# soldering_station.net
KiCad netlist of a schematic drawn in Altium Designer
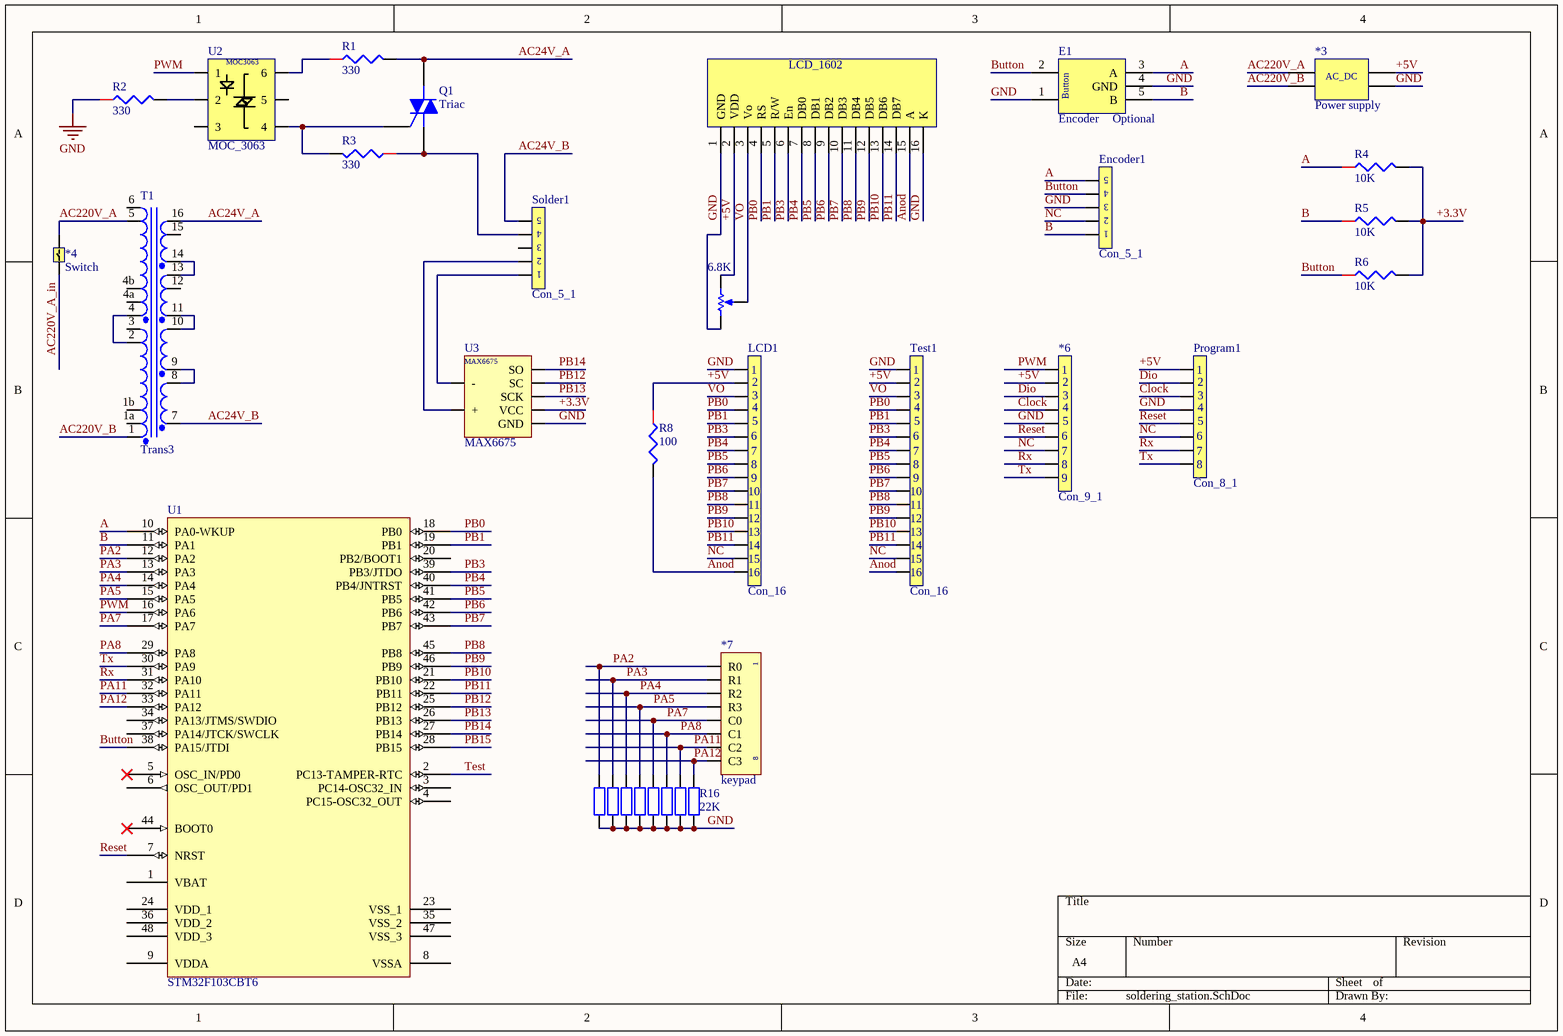
[diagram p0: soldering_station.SchDoc]

(export (version "E")
  (design (tool "Eeschema 10.0.6"))
  (components
    (comp (ref "*2") (value "LCD_1602") (libsource (lib "Armen_1") (part "LCD_1602")))
    (comp (ref "*3") (value "Power supply") (libsource (lib "Armen_1") (part "Power supply")))
    (comp (ref "*4") (value "Switch") (libsource (lib "Armen_1") (part "Switch_3_small")))
    (comp (ref "*6") (value "Con_9_1") (libsource (lib "Armen_1") (part "Con_9_1")))
    (comp (ref "*7") (value "keypad") (libsource (lib "Armen_1") (part "keypad")))
    (comp (ref "E1") (value "Encoder") (libsource (lib "Armen_1") (part "Encoder")))
    (comp (ref "Encoder1") (value "Con_5_1") (libsource (lib "Armen_1") (part "Con_5_1")))
    (comp (ref "LCD1") (value "Con_16") (libsource (lib "Armen_1") (part "Con_16")))
    (comp (ref "Program1") (value "Con_8_1") (libsource (lib "Armen_1") (part "Con_8_1")))
    (comp (ref "Q1")
      (value "Triac")
      (footprint "369-03")
      (description "Silicon Bidirectional Triode Thyristor")
      (fields (field (name "PUBLISHER") "Altium Limited"))
      (libsource (lib "Miscellaneous Devices") (part "Triac"))
    )
    (comp (ref "R1")
      (value "330")
      (footprint "Chip2PinSM127P600-8N")
      (description "RES SMD 1K OHM 0.1% 1/10W 0603")
      (fields
        (field (name "DIGI-KEY PART NUMBER") "P1.0KDBCT-ND")
        (field (name "MANUFACTURER PART NUMBER") "ERA-3AEB102V")
      )
      (libsource (lib "Wash_Control") (part "Resistor_1K"))
    )
    (comp (ref "R2")
      (value "330")
      (footprint "Chip2PinSM127P600-8N")
      (description "RES SMD 1K OHM 0.1% 1/10W 0603")
      (fields
        (field (name "DIGI-KEY PART NUMBER") "P1.0KDBCT-ND")
        (field (name "MANUFACTURER PART NUMBER") "ERA-3AEB102V")
      )
      (libsource (lib "Wash_Control") (part "Resistor_1K"))
    )
    (comp (ref "R3")
      (value "330")
      (footprint "Chip2PinSM127P600-8N")
      (description "RES SMD 1K OHM 0.1% 1/10W 0603")
      (fields
        (field (name "DIGI-KEY PART NUMBER") "P1.0KDBCT-ND")
        (field (name "MANUFACTURER PART NUMBER") "ERA-3AEB102V")
      )
      (libsource (lib "Wash_Control") (part "Resistor_1K"))
    )
    (comp (ref "R4")
      (value "10K")
      (footprint "Chip2PinSM127P600-8N")
      (description "RES SMD 10K OHM 0.5% 1/16W 0603")
      (fields
        (field (name "DIGI-KEY PART NUMBER") "RR08P10.0KDTR-ND")
        (field (name "MANUFACTURER PART NUMBER") "RR0816P-103-D")
      )
      (libsource (lib "Wash_Control") (part "Resistor_10k Ohm"))
    )
    (comp (ref "R5")
      (value "10K")
      (footprint "Chip2PinSM127P600-8N")
      (description "RES SMD 10K OHM 0.5% 1/16W 0603")
      (fields
        (field (name "DIGI-KEY PART NUMBER") "RR08P10.0KDTR-ND")
        (field (name "MANUFACTURER PART NUMBER") "RR0816P-103-D")
      )
      (libsource (lib "Wash_Control") (part "Resistor_10k Ohm"))
    )
    (comp (ref "R6")
      (value "10K")
      (footprint "Chip2PinSM127P600-8N")
      (description "RES SMD 10K OHM 0.5% 1/16W 0603")
      (fields
        (field (name "DIGI-KEY PART NUMBER") "RR08P10.0KDTR-ND")
        (field (name "MANUFACTURER PART NUMBER") "RR0816P-103-D")
      )
      (libsource (lib "Wash_Control") (part "Resistor_10k Ohm"))
    )
    (comp (ref "R7")
      (value "6.8K")
      (footprint "VR5")
      (description "Potentiometer")
      (fields (field (name "Comment") "RPot") (field (name "PUBLISHER") "Altium Limited"))
      (libsource (lib "Miscellaneous Devices") (part "RPot"))
    )
    (comp (ref "R8")
      (value "100")
      (footprint "Chip2PinSM127P600-8N")
      (description "RES SMD 1K OHM 0.1% 1/10W 0603")
      (fields
        (field (name "DIGI-KEY PART NUMBER") "P1.0KDBCT-ND")
        (field (name "MANUFACTURER PART NUMBER") "ERA-3AEB102V")
      )
      (libsource (lib "Wash_Control") (part "Resistor_1K"))
    )
    (comp (ref "R9")
      (value "20K")
      (footprint "AXIAL-0.4")
      (description "Resistor")
      (libsource (lib "Ar_MainBoard_RPD_") (part "Res2"))
    )
    (comp (ref "R10")
      (value "20K")
      (footprint "AXIAL-0.4")
      (description "Resistor")
      (libsource (lib "Ar_MainBoard_RPD_") (part "Res2"))
    )
    (comp (ref "R11")
      (value "20K")
      (footprint "AXIAL-0.4")
      (description "Resistor")
      (libsource (lib "Ar_MainBoard_RPD_") (part "Res2"))
    )
    (comp (ref "R12")
      (value "20K")
      (footprint "AXIAL-0.4")
      (description "Resistor")
      (libsource (lib "Ar_MainBoard_RPD_") (part "Res2"))
    )
    (comp (ref "R13")
      (value "20K")
      (footprint "AXIAL-0.4")
      (description "Resistor")
      (libsource (lib "Ar_MainBoard_RPD_") (part "Res2"))
    )
    (comp (ref "R14")
      (value "20K")
      (footprint "AXIAL-0.4")
      (description "Resistor")
      (libsource (lib "Ar_MainBoard_RPD_") (part "Res2"))
    )
    (comp (ref "R15")
      (value "20K")
      (footprint "AXIAL-0.4")
      (description "Resistor")
      (libsource (lib "Ar_MainBoard_RPD_") (part "Res2"))
    )
    (comp (ref "R16")
      (value "22K")
      (footprint "AXIAL-0.4")
      (description "Resistor")
      (libsource (lib "Ar_MainBoard_RPD_") (part "Res2"))
    )
    (comp (ref "Solder1") (value "Con_5_1") (libsource (lib "Armen_1") (part "Con_5_1")))
    (comp (ref "T1")
      (value "Trans3")
      (footprint "TRF_6")
      (description "Three-winding Transformer (Non-Ideal)")
      (fields (field (name "PUBLISHER") "Altium Limited"))
      (libsource (lib "Soldering_station") (part "Trans3_1"))
    )
    (comp (ref "Test1") (value "Con_16") (libsource (lib "Armen_1") (part "Con_16")))
    (comp (ref "U1")
      (value "STM32F103CBT6")
      (footprint "LQFP48_N")
      (description "STM32 ARM-based 32-bit MCU with 128 Kbytes Flash, 48-pin LQFP, Industrial Temperature")
      (fields (field (name "PUBLISHER") "Altium Limited"))
      (libsource (lib "ST Microcontroller 32-Bit STM32") (part "STM32F103CBT6"))
    )
    (comp (ref "U2") (value "MOC_3063") (libsource (lib "Soldering_station") (part "MOC_3065")))
    (comp (ref "U3") (value "MAX6675") (libsource (lib "Armen_1") (part "MAX6675")))
  )
  (nets
    (net (code "1") (name "/+3.3V") (class "Default")
      (node (ref "R4") (pin "2") (pinfunction "2_2") (pintype "passive"))
      (node (ref "R5") (pin "2") (pinfunction "2_2") (pintype "passive"))
      (node (ref "R6") (pin "2") (pinfunction "2_2") (pintype "passive"))
      (node (ref "U3") (pin "6") (pinfunction "VCC_6") (pintype "passive"))
    )
    (net (code "2") (name "/+5V") (class "Default")
      (node (ref "*2") (pin "2") (pinfunction "VDD_2") (pintype "passive"))
      (node (ref "*3") (pin "30") (pinfunction "30_30") (pintype "passive"))
      (node (ref "*6") (pin "2") (pinfunction "2_2") (pintype "passive"))
      (node (ref "LCD1") (pin "2") (pinfunction "2_2") (pintype "passive"))
      (node (ref "Program1") (pin "1") (pinfunction "1_1") (pintype "passive"))
      (node (ref "R7") (pin "2") (pinfunction "BOT_2") (pintype "passive"))
      (node (ref "R8") (pin "1") (pinfunction "1_1") (pintype "passive"))
      (node (ref "Test1") (pin "2") (pinfunction "2_2") (pintype "passive"))
    )
    (net (code "3") (name "/A") (class "Default")
      (node (ref "E1") (pin "3") (pinfunction "A_3") (pintype "passive"))
      (node (ref "Encoder1") (pin "4") (pinfunction "4_4") (pintype "passive"))
      (node (ref "R4") (pin "1") (pinfunction "1_1") (pintype "passive"))
      (node (ref "U1") (pin "10") (pinfunction "PA0-WKUP_10") (pintype "bidirectional"))
    )
    (net (code "4") (name "/AC24V_A") (class "Default")
      (node (ref "Q1") (pin "2") (pinfunction "M2_2") (pintype "passive"))
      (node (ref "R1") (pin "2") (pinfunction "2_2") (pintype "passive"))
      (node (ref "T1") (pin "16") (pinfunction "16_16") (pintype "passive"))
    )
    (net (code "5") (name "/AC24V_B") (class "Default")
      (node (ref "Solder1") (pin "4") (pinfunction "4_4") (pintype "passive"))
      (node (ref "T1") (pin "7") (pinfunction "7_7") (pintype "passive"))
    )
    (net (code "6") (name "/AC220V_A") (class "Default")
      (node (ref "*3") (pin "32") (pinfunction "32_32") (pintype "passive"))
      (node (ref "*4") (pin "35") (pinfunction "35_35") (pintype "passive"))
      (node (ref "T1") (pin "5") (pinfunction "5_5") (pintype "passive"))
    )
    (net (code "7") (name "/AC220V_A_in") (class "Default")
      (node (ref "*4") (pin "34") (pinfunction "34_34") (pintype "passive"))
    )
    (net (code "8") (name "/AC220V_B") (class "Default")
      (node (ref "*3") (pin "33") (pinfunction "33_33") (pintype "passive"))
      (node (ref "T1") (pin "1") (pinfunction "1_1") (pintype "passive"))
    )
    (net (code "9") (name "/Anod") (class "Default")
      (node (ref "*2") (pin "15") (pinfunction "A_15") (pintype "passive"))
      (node (ref "LCD1") (pin "16") (pinfunction "16_16") (pintype "passive"))
      (node (ref "R8") (pin "2") (pinfunction "2_2") (pintype "passive"))
      (node (ref "Test1") (pin "16") (pinfunction "16_16") (pintype "passive"))
    )
    (net (code "10") (name "/B") (class "Default")
      (node (ref "E1") (pin "5") (pinfunction "B_5") (pintype "passive"))
      (node (ref "Encoder1") (pin "0") (pinfunction "0_0") (pintype "passive"))
      (node (ref "R5") (pin "1") (pinfunction "1_1") (pintype "passive"))
      (node (ref "U1") (pin "11") (pinfunction "PA1_11") (pintype "bidirectional"))
    )
    (net (code "11") (name "/Button") (class "Default")
      (node (ref "E1") (pin "2") (pintype "passive"))
      (node (ref "Encoder1") (pin "3") (pinfunction "3_3") (pintype "passive"))
      (node (ref "R6") (pin "1") (pinfunction "1_1") (pintype "passive"))
      (node (ref "U1") (pin "38") (pinfunction "PA15/JTDI_38") (pintype "bidirectional"))
    )
    (net (code "12") (name "/Clock") (class "Default")
      (node (ref "*6") (pin "4") (pinfunction "4_4") (pintype "passive"))
      (node (ref "Program1") (pin "3") (pinfunction "3_3") (pintype "passive"))
    )
    (net (code "13") (name "/Dio") (class "Default")
      (node (ref "*6") (pin "3") (pinfunction "3_3") (pintype "passive"))
      (node (ref "Program1") (pin "2") (pinfunction "2_2") (pintype "passive"))
    )
    (net (code "14") (name "/NC") (class "Default")
      (node (ref "*6") (pin "7") (pinfunction "7_7") (pintype "passive"))
      (node (ref "Encoder1") (pin "1") (pinfunction "1_1") (pintype "passive"))
      (node (ref "LCD1") (pin "15") (pinfunction "15_15") (pintype "passive"))
      (node (ref "Program1") (pin "6") (pinfunction "6_6") (pintype "passive"))
      (node (ref "Test1") (pin "15") (pinfunction "15_15") (pintype "passive"))
    )
    (net (code "15") (name "/PA2") (class "Default")
      (node (ref "*7") (pin "1") (pinfunction "R0_1") (pintype "passive"))
      (node (ref "R9") (pin "2") (pinfunction "2_2") (pintype "passive"))
      (node (ref "U1") (pin "12") (pinfunction "PA2_12") (pintype "bidirectional"))
    )
    (net (code "16") (name "/PA3") (class "Default")
      (node (ref "*7") (pin "2") (pinfunction "R1_2") (pintype "passive"))
      (node (ref "R10") (pin "2") (pinfunction "2_2") (pintype "passive"))
      (node (ref "U1") (pin "13") (pinfunction "PA3_13") (pintype "bidirectional"))
    )
    (net (code "17") (name "/PA4") (class "Default")
      (node (ref "*7") (pin "3") (pinfunction "R2_3") (pintype "passive"))
      (node (ref "R11") (pin "2") (pinfunction "2_2") (pintype "passive"))
      (node (ref "U1") (pin "14") (pinfunction "PA4_14") (pintype "bidirectional"))
    )
    (net (code "18") (name "/PA5") (class "Default")
      (node (ref "*7") (pin "4") (pinfunction "R3_4") (pintype "passive"))
      (node (ref "R12") (pin "2") (pinfunction "2_2") (pintype "passive"))
      (node (ref "U1") (pin "15") (pinfunction "PA5_15") (pintype "bidirectional"))
    )
    (net (code "19") (name "/PA7") (class "Default")
      (node (ref "*7") (pin "5") (pinfunction "C0_5") (pintype "passive"))
      (node (ref "R13") (pin "2") (pinfunction "2_2") (pintype "passive"))
      (node (ref "U1") (pin "17") (pinfunction "PA7_17") (pintype "bidirectional"))
    )
    (net (code "20") (name "/PA8") (class "Default")
      (node (ref "*7") (pin "6") (pinfunction "C1_6") (pintype "passive"))
      (node (ref "R14") (pin "2") (pinfunction "2_2") (pintype "passive"))
      (node (ref "U1") (pin "29") (pinfunction "PA8_29") (pintype "bidirectional"))
    )
    (net (code "21") (name "/PA11") (class "Default")
      (node (ref "*7") (pin "7") (pinfunction "C2_7") (pintype "passive"))
      (node (ref "R15") (pin "2") (pinfunction "2_2") (pintype "passive"))
      (node (ref "U1") (pin "32") (pinfunction "PA11_32") (pintype "bidirectional"))
    )
    (net (code "22") (name "/PA12") (class "Default")
      (node (ref "*7") (pin "8") (pinfunction "C3_8") (pintype "passive"))
      (node (ref "R16") (pin "2") (pinfunction "2_2") (pintype "passive"))
      (node (ref "U1") (pin "33") (pinfunction "PA12_33") (pintype "bidirectional"))
    )
    (net (code "23") (name "/PB0") (class "Default")
      (node (ref "*2") (pin "4") (pinfunction "RS_4") (pintype "passive"))
      (node (ref "LCD1") (pin "4") (pinfunction "4_4") (pintype "passive"))
      (node (ref "Test1") (pin "4") (pinfunction "4_4") (pintype "passive"))
      (node (ref "U1") (pin "18") (pinfunction "PB0_18") (pintype "bidirectional"))
    )
    (net (code "24") (name "/PB1") (class "Default")
      (node (ref "*2") (pin "5") (pinfunction "R/W_5") (pintype "passive"))
      (node (ref "LCD1") (pin "5") (pinfunction "5_5") (pintype "passive"))
      (node (ref "Test1") (pin "5") (pinfunction "5_5") (pintype "passive"))
      (node (ref "U1") (pin "19") (pinfunction "PB1_19") (pintype "bidirectional"))
    )
    (net (code "25") (name "/PB3") (class "Default")
      (node (ref "*2") (pin "6") (pinfunction "En_6") (pintype "passive"))
      (node (ref "LCD1") (pin "6") (pinfunction "6_6") (pintype "passive"))
      (node (ref "Test1") (pin "6") (pinfunction "6_6") (pintype "passive"))
      (node (ref "U1") (pin "39") (pinfunction "PB3/JTDO_39") (pintype "bidirectional"))
    )
    (net (code "26") (name "/PB4") (class "Default")
      (node (ref "*2") (pin "7") (pinfunction "DB0_7") (pintype "passive"))
      (node (ref "LCD1") (pin "7") (pinfunction "7_7") (pintype "passive"))
      (node (ref "Test1") (pin "7") (pinfunction "7_7") (pintype "passive"))
      (node (ref "U1") (pin "40") (pinfunction "PB4/JNTRST_40") (pintype "bidirectional"))
    )
    (net (code "27") (name "/PB5") (class "Default")
      (node (ref "*2") (pin "8") (pinfunction "DB1_8") (pintype "passive"))
      (node (ref "LCD1") (pin "8") (pinfunction "8_8") (pintype "passive"))
      (node (ref "Test1") (pin "8") (pinfunction "8_8") (pintype "passive"))
      (node (ref "U1") (pin "41") (pinfunction "PB5_41") (pintype "bidirectional"))
    )
    (net (code "28") (name "/PB6") (class "Default")
      (node (ref "*2") (pin "9") (pinfunction "DB2_9") (pintype "passive"))
      (node (ref "LCD1") (pin "9") (pinfunction "9_9") (pintype "passive"))
      (node (ref "Test1") (pin "9") (pinfunction "9_9") (pintype "passive"))
      (node (ref "U1") (pin "42") (pinfunction "PB6_42") (pintype "bidirectional"))
    )
    (net (code "29") (name "/PB7") (class "Default")
      (node (ref "*2") (pin "10") (pinfunction "DB3_10") (pintype "passive"))
      (node (ref "LCD1") (pin "10") (pinfunction "10_10") (pintype "passive"))
      (node (ref "Test1") (pin "10") (pinfunction "10_10") (pintype "passive"))
      (node (ref "U1") (pin "43") (pinfunction "PB7_43") (pintype "bidirectional"))
    )
    (net (code "30") (name "/PB8") (class "Default")
      (node (ref "*2") (pin "11") (pinfunction "DB4_11") (pintype "passive"))
      (node (ref "LCD1") (pin "11") (pinfunction "11_11") (pintype "passive"))
      (node (ref "Test1") (pin "11") (pinfunction "11_11") (pintype "passive"))
      (node (ref "U1") (pin "45") (pinfunction "PB8_45") (pintype "bidirectional"))
    )
    (net (code "31") (name "/PB9") (class "Default")
      (node (ref "*2") (pin "12") (pinfunction "DB5_12") (pintype "passive"))
      (node (ref "LCD1") (pin "12") (pinfunction "12_12") (pintype "passive"))
      (node (ref "Test1") (pin "12") (pinfunction "12_12") (pintype "passive"))
      (node (ref "U1") (pin "46") (pinfunction "PB9_46") (pintype "bidirectional"))
    )
    (net (code "32") (name "/PB10") (class "Default")
      (node (ref "*2") (pin "13") (pinfunction "DB6_13") (pintype "passive"))
      (node (ref "LCD1") (pin "13") (pinfunction "13_13") (pintype "passive"))
      (node (ref "Test1") (pin "13") (pinfunction "13_13") (pintype "passive"))
      (node (ref "U1") (pin "21") (pinfunction "PB10_21") (pintype "bidirectional"))
    )
    (net (code "33") (name "/PB11") (class "Default")
      (node (ref "*2") (pin "14") (pinfunction "DB7_14") (pintype "passive"))
      (node (ref "LCD1") (pin "14") (pinfunction "14_14") (pintype "passive"))
      (node (ref "Test1") (pin "14") (pinfunction "14_14") (pintype "passive"))
      (node (ref "U1") (pin "22") (pinfunction "PB11_22") (pintype "bidirectional"))
    )
    (net (code "34") (name "/PB12") (class "Default")
      (node (ref "U1") (pin "25") (pinfunction "PB12_25") (pintype "bidirectional"))
      (node (ref "U3") (pin "4") (pinfunction "SC_4") (pintype "passive"))
    )
    (net (code "35") (name "/PB13") (class "Default")
      (node (ref "U1") (pin "26") (pinfunction "PB13_26") (pintype "bidirectional"))
      (node (ref "U3") (pin "5") (pinfunction "SCK_5") (pintype "passive"))
    )
    (net (code "36") (name "/PB14") (class "Default")
      (node (ref "U1") (pin "27") (pinfunction "PB14_27") (pintype "bidirectional"))
      (node (ref "U3") (pin "3") (pinfunction "SO_3") (pintype "passive"))
    )
    (net (code "37") (name "/PB15") (class "Default")
      (node (ref "U1") (pin "28") (pinfunction "PB15_28") (pintype "bidirectional"))
    )
    (net (code "38") (name "/PWM") (class "Default")
      (node (ref "*6") (pin "1") (pinfunction "1_1") (pintype "passive"))
      (node (ref "U1") (pin "16") (pinfunction "PA6_16") (pintype "bidirectional"))
      (node (ref "U2") (pin "1") (pinfunction "1_1") (pintype "passive"))
    )
    (net (code "39") (name "/Reset") (class "Default")
      (node (ref "*6") (pin "6") (pinfunction "6_6") (pintype "passive"))
      (node (ref "Program1") (pin "5") (pinfunction "5_5") (pintype "passive"))
      (node (ref "U1") (pin "7") (pinfunction "NRST_7") (pintype "bidirectional"))
    )
    (net (code "40") (name "/Rx") (class "Default")
      (node (ref "*6") (pin "8") (pinfunction "8_8") (pintype "passive"))
      (node (ref "Program1") (pin "7") (pinfunction "7_7") (pintype "passive"))
      (node (ref "U1") (pin "31") (pinfunction "PA10_31") (pintype "bidirectional"))
    )
    (net (code "41") (name "/Test") (class "Default")
      (node (ref "U1") (pin "2") (pinfunction "PC13-TAMPER-RTC_2") (pintype "bidirectional"))
    )
    (net (code "42") (name "/Tx") (class "Default")
      (node (ref "*6") (pin "9") (pinfunction "9_9") (pintype "passive"))
      (node (ref "Program1") (pin "8") (pinfunction "8_8") (pintype "passive"))
      (node (ref "U1") (pin "30") (pinfunction "PA9_30") (pintype "bidirectional"))
    )
    (net (code "43") (name "/VO") (class "Default")
      (node (ref "*2") (pin "3") (pinfunction "Vo_3") (pintype "passive"))
      (node (ref "LCD1") (pin "3") (pinfunction "3_3") (pintype "passive"))
      (node (ref "R7") (pin "3") (pinfunction "TAP_3") (pintype "passive"))
      (node (ref "Test1") (pin "3") (pinfunction "3_3") (pintype "passive"))
    )
    (net (code "44") (name "GND") (class "Default")
      (node (ref "*2") (pin "1") (pinfunction "GND_1") (pintype "passive"))
      (node (ref "*2") (pin "16") (pinfunction "K_16") (pintype "passive"))
      (node (ref "*3") (pin "31") (pinfunction "31_31") (pintype "passive"))
      (node (ref "*6") (pin "5") (pinfunction "5_5") (pintype "passive"))
      (node (ref "E1") (pin "1") (pintype "passive"))
      (node (ref "E1") (pin "4") (pinfunction "GND_4") (pintype "passive"))
      (node (ref "Encoder1") (pin "2") (pinfunction "2_2") (pintype "passive"))
      (node (ref "LCD1") (pin "1") (pinfunction "1_1") (pintype "passive"))
      (node (ref "Program1") (pin "4") (pinfunction "4_4") (pintype "passive"))
      (node (ref "R10") (pin "1") (pinfunction "1_1") (pintype "passive"))
      (node (ref "R11") (pin "1") (pinfunction "1_1") (pintype "passive"))
      (node (ref "R12") (pin "1") (pinfunction "1_1") (pintype "passive"))
      (node (ref "R13") (pin "1") (pinfunction "1_1") (pintype "passive"))
      (node (ref "R14") (pin "1") (pinfunction "1_1") (pintype "passive"))
      (node (ref "R15") (pin "1") (pinfunction "1_1") (pintype "passive"))
      (node (ref "R16") (pin "1") (pinfunction "1_1") (pintype "passive"))
      (node (ref "R2") (pin "1") (pinfunction "1_1") (pintype "passive"))
      (node (ref "R7") (pin "1") (pinfunction "TOP_1") (pintype "passive"))
      (node (ref "R9") (pin "1") (pinfunction "1_1") (pintype "passive"))
      (node (ref "Test1") (pin "1") (pinfunction "1_1") (pintype "passive"))
      (node (ref "U3") (pin "7") (pinfunction "GND_7") (pintype "passive"))
    )
    (net (code "45") (name "Net-(Q1-G)") (class "Default")
      (node (ref "Q1") (pin "3") (pinfunction "G_3") (pintype "passive"))
      (node (ref "R3") (pin "2") (pinfunction "2_2") (pintype "passive"))
      (node (ref "U2") (pin "4") (pinfunction "4_4") (pintype "passive"))
    )
    (net (code "46") (name "Net-(Q1-M1)") (class "Default")
      (node (ref "Q1") (pin "1") (pinfunction "M1_1") (pintype "passive"))
      (node (ref "R3") (pin "1") (pinfunction "1_1") (pintype "passive"))
      (node (ref "Solder1") (pin "3") (pinfunction "3_3") (pintype "passive"))
    )
    (net (code "47") (name "Net-(R1-Pad1)") (class "Default")
      (node (ref "R1") (pin "1") (pinfunction "1_1") (pintype "passive"))
      (node (ref "U2") (pin "6") (pinfunction "6_6") (pintype "passive"))
    )
    (net (code "48") (name "Net-(R2-Pad2)") (class "Default")
      (node (ref "R2") (pin "2") (pinfunction "2_2") (pintype "passive"))
      (node (ref "U2") (pin "2") (pinfunction "2_2") (pintype "passive"))
    )
    (net (code "49") (name "Net-(T1-Pad2)") (class "Default")
      (node (ref "T1") (pin "2") (pinfunction "2_2") (pintype "passive"))
      (node (ref "T1") (pin "4") (pinfunction "4_4") (pintype "passive"))
    )
    (net (code "50") (name "Net-(T1-Pad8)") (class "Default")
      (node (ref "T1") (pin "8") (pinfunction "8_8") (pintype "passive"))
      (node (ref "T1") (pin "9") (pinfunction "9_9") (pintype "passive"))
    )
    (net (code "51") (name "Net-(T1-Pad10)") (class "Default")
      (node (ref "T1") (pin "10") (pinfunction "10_10") (pintype "passive"))
      (node (ref "T1") (pin "11") (pinfunction "11_11") (pintype "passive"))
    )
    (net (code "52") (name "Net-(T1-Pad13)") (class "Default")
      (node (ref "T1") (pin "13") (pinfunction "13_13") (pintype "passive"))
      (node (ref "T1") (pin "14") (pinfunction "14_14") (pintype "passive"))
    )
    (net (code "53") (name "Net-(U3-+)") (class "Default")
      (node (ref "Solder1") (pin "1") (pinfunction "1_1") (pintype "passive"))
      (node (ref "U3") (pin "2") (pinfunction "+_2") (pintype "passive"))
    )
    (net (code "54") (name "Net-(U3--)") (class "Default")
      (node (ref "Solder1") (pin "0") (pinfunction "0_0") (pintype "passive"))
      (node (ref "U3") (pin "1") (pinfunction "-_1") (pintype "passive"))
    )
    (net (code "55") (name "unconnected-(Solder1-Pad2)") (class "Default")
      (node (ref "Solder1") (pin "2") (pinfunction "2_2") (pintype "passive"))
    )
    (net (code "56") (name "unconnected-(T1-Pad1a)") (class "Default")
      (node (ref "T1") (pin "1a") (pinfunction "1a_1a") (pintype "passive"))
    )
    (net (code "57") (name "unconnected-(T1-Pad1b)") (class "Default")
      (node (ref "T1") (pin "1b") (pinfunction "1b_1b") (pintype "passive"))
    )
    (net (code "58") (name "unconnected-(T1-Pad3)") (class "Default")
      (node (ref "T1") (pin "3") (pinfunction "3_3") (pintype "passive"))
    )
    (net (code "59") (name "unconnected-(T1-Pad4a)") (class "Default")
      (node (ref "T1") (pin "4a") (pinfunction "4a_4a") (pintype "passive"))
    )
    (net (code "60") (name "unconnected-(T1-Pad4b)") (class "Default")
      (node (ref "T1") (pin "4b") (pinfunction "4b_4b") (pintype "passive"))
    )
    (net (code "61") (name "unconnected-(T1-Pad6)") (class "Default")
      (node (ref "T1") (pin "6") (pinfunction "6_6") (pintype "passive"))
    )
    (net (code "62") (name "unconnected-(T1-Pad12)") (class "Default")
      (node (ref "T1") (pin "12") (pinfunction "12_12") (pintype "passive"))
    )
    (net (code "63") (name "unconnected-(T1-Pad15)") (class "Default")
      (node (ref "T1") (pin "15") (pinfunction "15_15") (pintype "passive"))
    )
    (net (code "64") (name "unconnected-(U1-BOOT0-Pad44)") (class "Default")
      (node (ref "U1") (pin "44") (pinfunction "BOOT0_44") (pintype "input+no_connect"))
    )
    (net (code "65") (name "unconnected-(U1-OSC_IN{slash}PD0-Pad5)") (class "Default")
      (node (ref "U1") (pin "5") (pinfunction "OSC_IN/PD0_5") (pintype "input+no_connect"))
    )
    (net (code "66") (name "unconnected-(U1-OSC_OUT{slash}PD1-Pad6)") (class "Default")
      (node (ref "U1") (pin "6") (pinfunction "OSC_OUT/PD1_6") (pintype "output"))
    )
    (net (code "67") (name "unconnected-(U1-PA13{slash}JTMS{slash}SWDIO-Pad34)") (class "Default")
      (node (ref "U1") (pin "34") (pinfunction "PA13/JTMS/SWDIO_34") (pintype "bidirectional"))
    )
    (net (code "68") (name "unconnected-(U1-PA14{slash}JTCK{slash}SWCLK-Pad37)") (class "Default")
      (node (ref "U1") (pin "37") (pinfunction "PA14/JTCK/SWCLK_37") (pintype "bidirectional"))
    )
    (net (code "69") (name "unconnected-(U1-PB2{slash}BOOT1-Pad20)") (class "Default")
      (node (ref "U1") (pin "20") (pinfunction "PB2/BOOT1_20") (pintype "bidirectional"))
    )
    (net (code "70") (name "unconnected-(U1-PC14-OSC32_IN-Pad3)") (class "Default")
      (node (ref "U1") (pin "3") (pinfunction "PC14-OSC32_IN_3") (pintype "bidirectional"))
    )
    (net (code "71") (name "unconnected-(U1-PC15-OSC32_OUT-Pad4)") (class "Default")
      (node (ref "U1") (pin "4") (pinfunction "PC15-OSC32_OUT_4") (pintype "bidirectional"))
    )
    (net (code "72") (name "unconnected-(U1-VBAT-Pad1)") (class "Default")
      (node (ref "U1") (pin "1") (pinfunction "VBAT_1") (pintype "power_in"))
    )
    (net (code "73") (name "unconnected-(U1-VDDA-Pad9)") (class "Default")
      (node (ref "U1") (pin "9") (pinfunction "VDDA_9") (pintype "power_in"))
    )
    (net (code "74") (name "unconnected-(U1-VDD_1-Pad24)") (class "Default")
      (node (ref "U1") (pin "24") (pinfunction "VDD_1_24") (pintype "power_in"))
    )
    (net (code "75") (name "unconnected-(U1-VDD_2-Pad36)") (class "Default")
      (node (ref "U1") (pin "36") (pinfunction "VDD_2_36") (pintype "power_in"))
    )
    (net (code "76") (name "unconnected-(U1-VDD_3-Pad48)") (class "Default")
      (node (ref "U1") (pin "48") (pinfunction "VDD_3_48") (pintype "power_in"))
    )
    (net (code "77") (name "unconnected-(U1-VSSA-Pad8)") (class "Default")
      (node (ref "U1") (pin "8") (pinfunction "VSSA_8") (pintype "power_in"))
    )
    (net (code "78") (name "unconnected-(U1-VSS_1-Pad23)") (class "Default")
      (node (ref "U1") (pin "23") (pinfunction "VSS_1_23") (pintype "power_in"))
    )
    (net (code "79") (name "unconnected-(U1-VSS_2-Pad35)") (class "Default")
      (node (ref "U1") (pin "35") (pinfunction "VSS_2_35") (pintype "power_in"))
    )
    (net (code "80") (name "unconnected-(U1-VSS_3-Pad47)") (class "Default")
      (node (ref "U1") (pin "47") (pinfunction "VSS_3_47") (pintype "power_in"))
    )
    (net (code "81") (name "unconnected-(U2-Pad3)") (class "Default")
      (node (ref "U2") (pin "3") (pinfunction "3_3") (pintype "passive"))
    )
    (net (code "82") (name "unconnected-(U2-Pad5)") (class "Default")
      (node (ref "U2") (pin "5") (pinfunction "5_5") (pintype "passive"))
    )
  )
)
